# Connectors_-_RP2040_Advanced_Breakout_Bo.net
KiCad netlist of a schematic drawn in EasyEDA
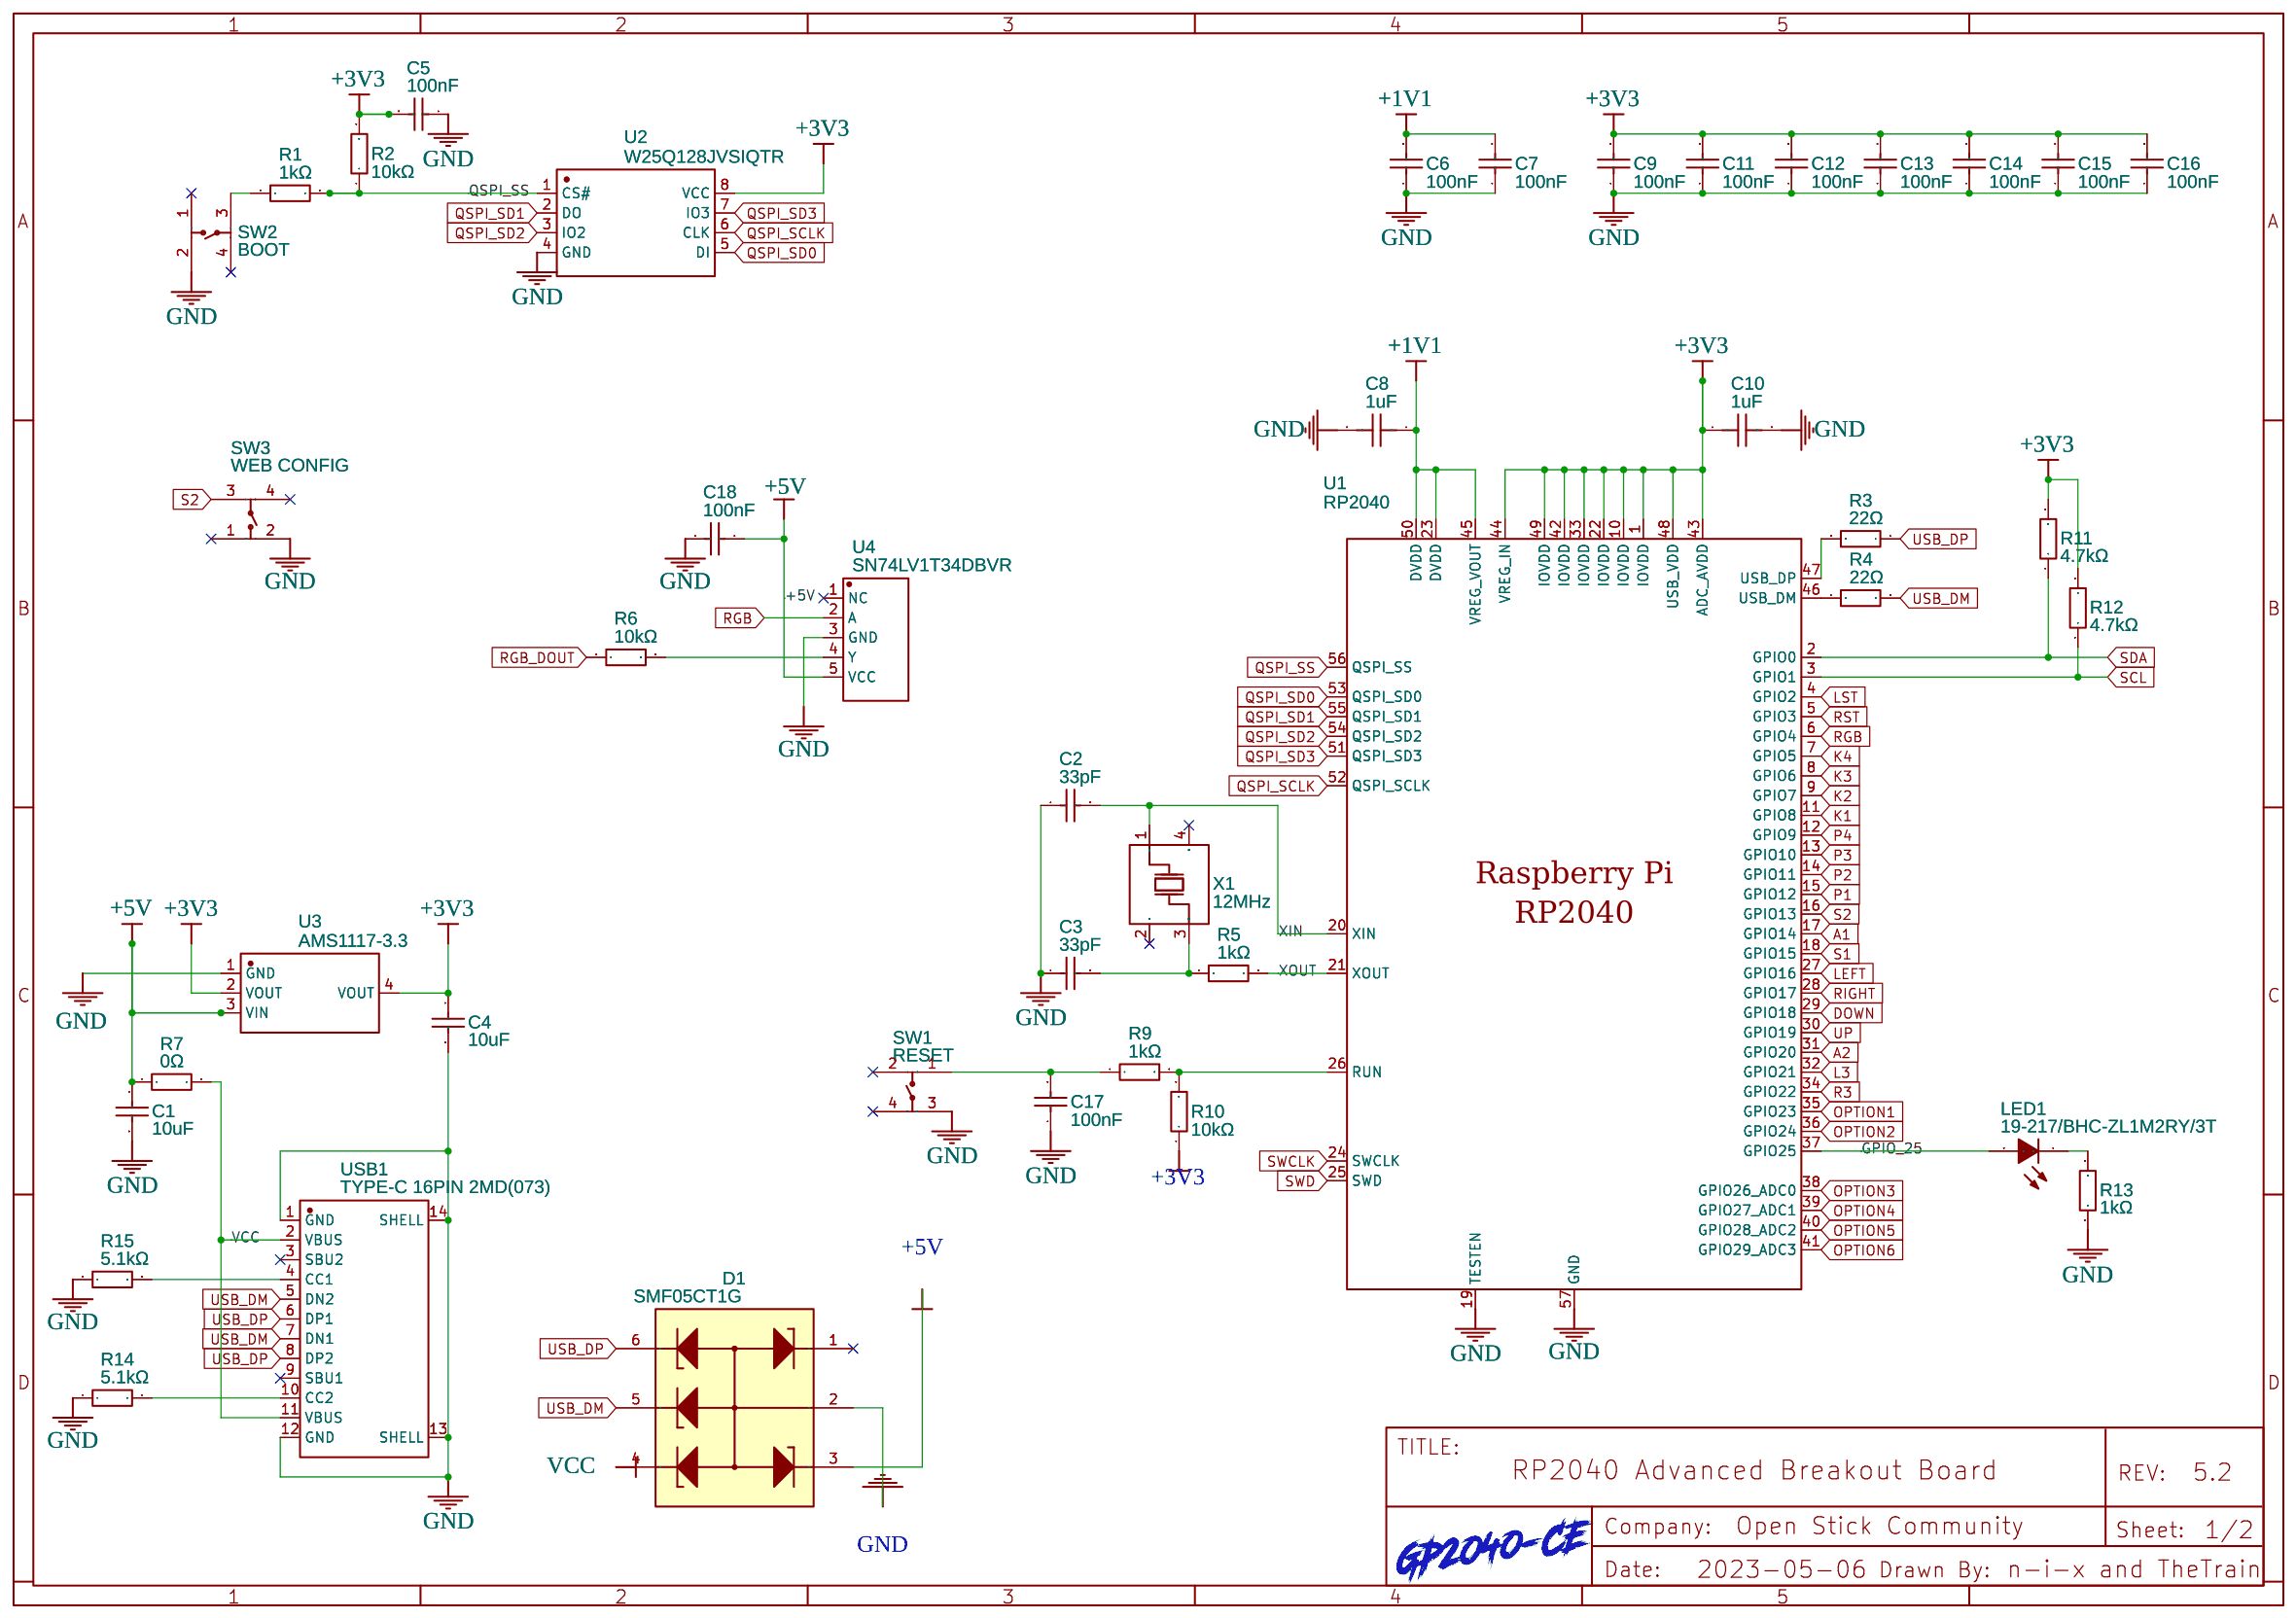
[diagram p0: RP2040 Advanced Breakout Board - Version 5.2E - Schematics]
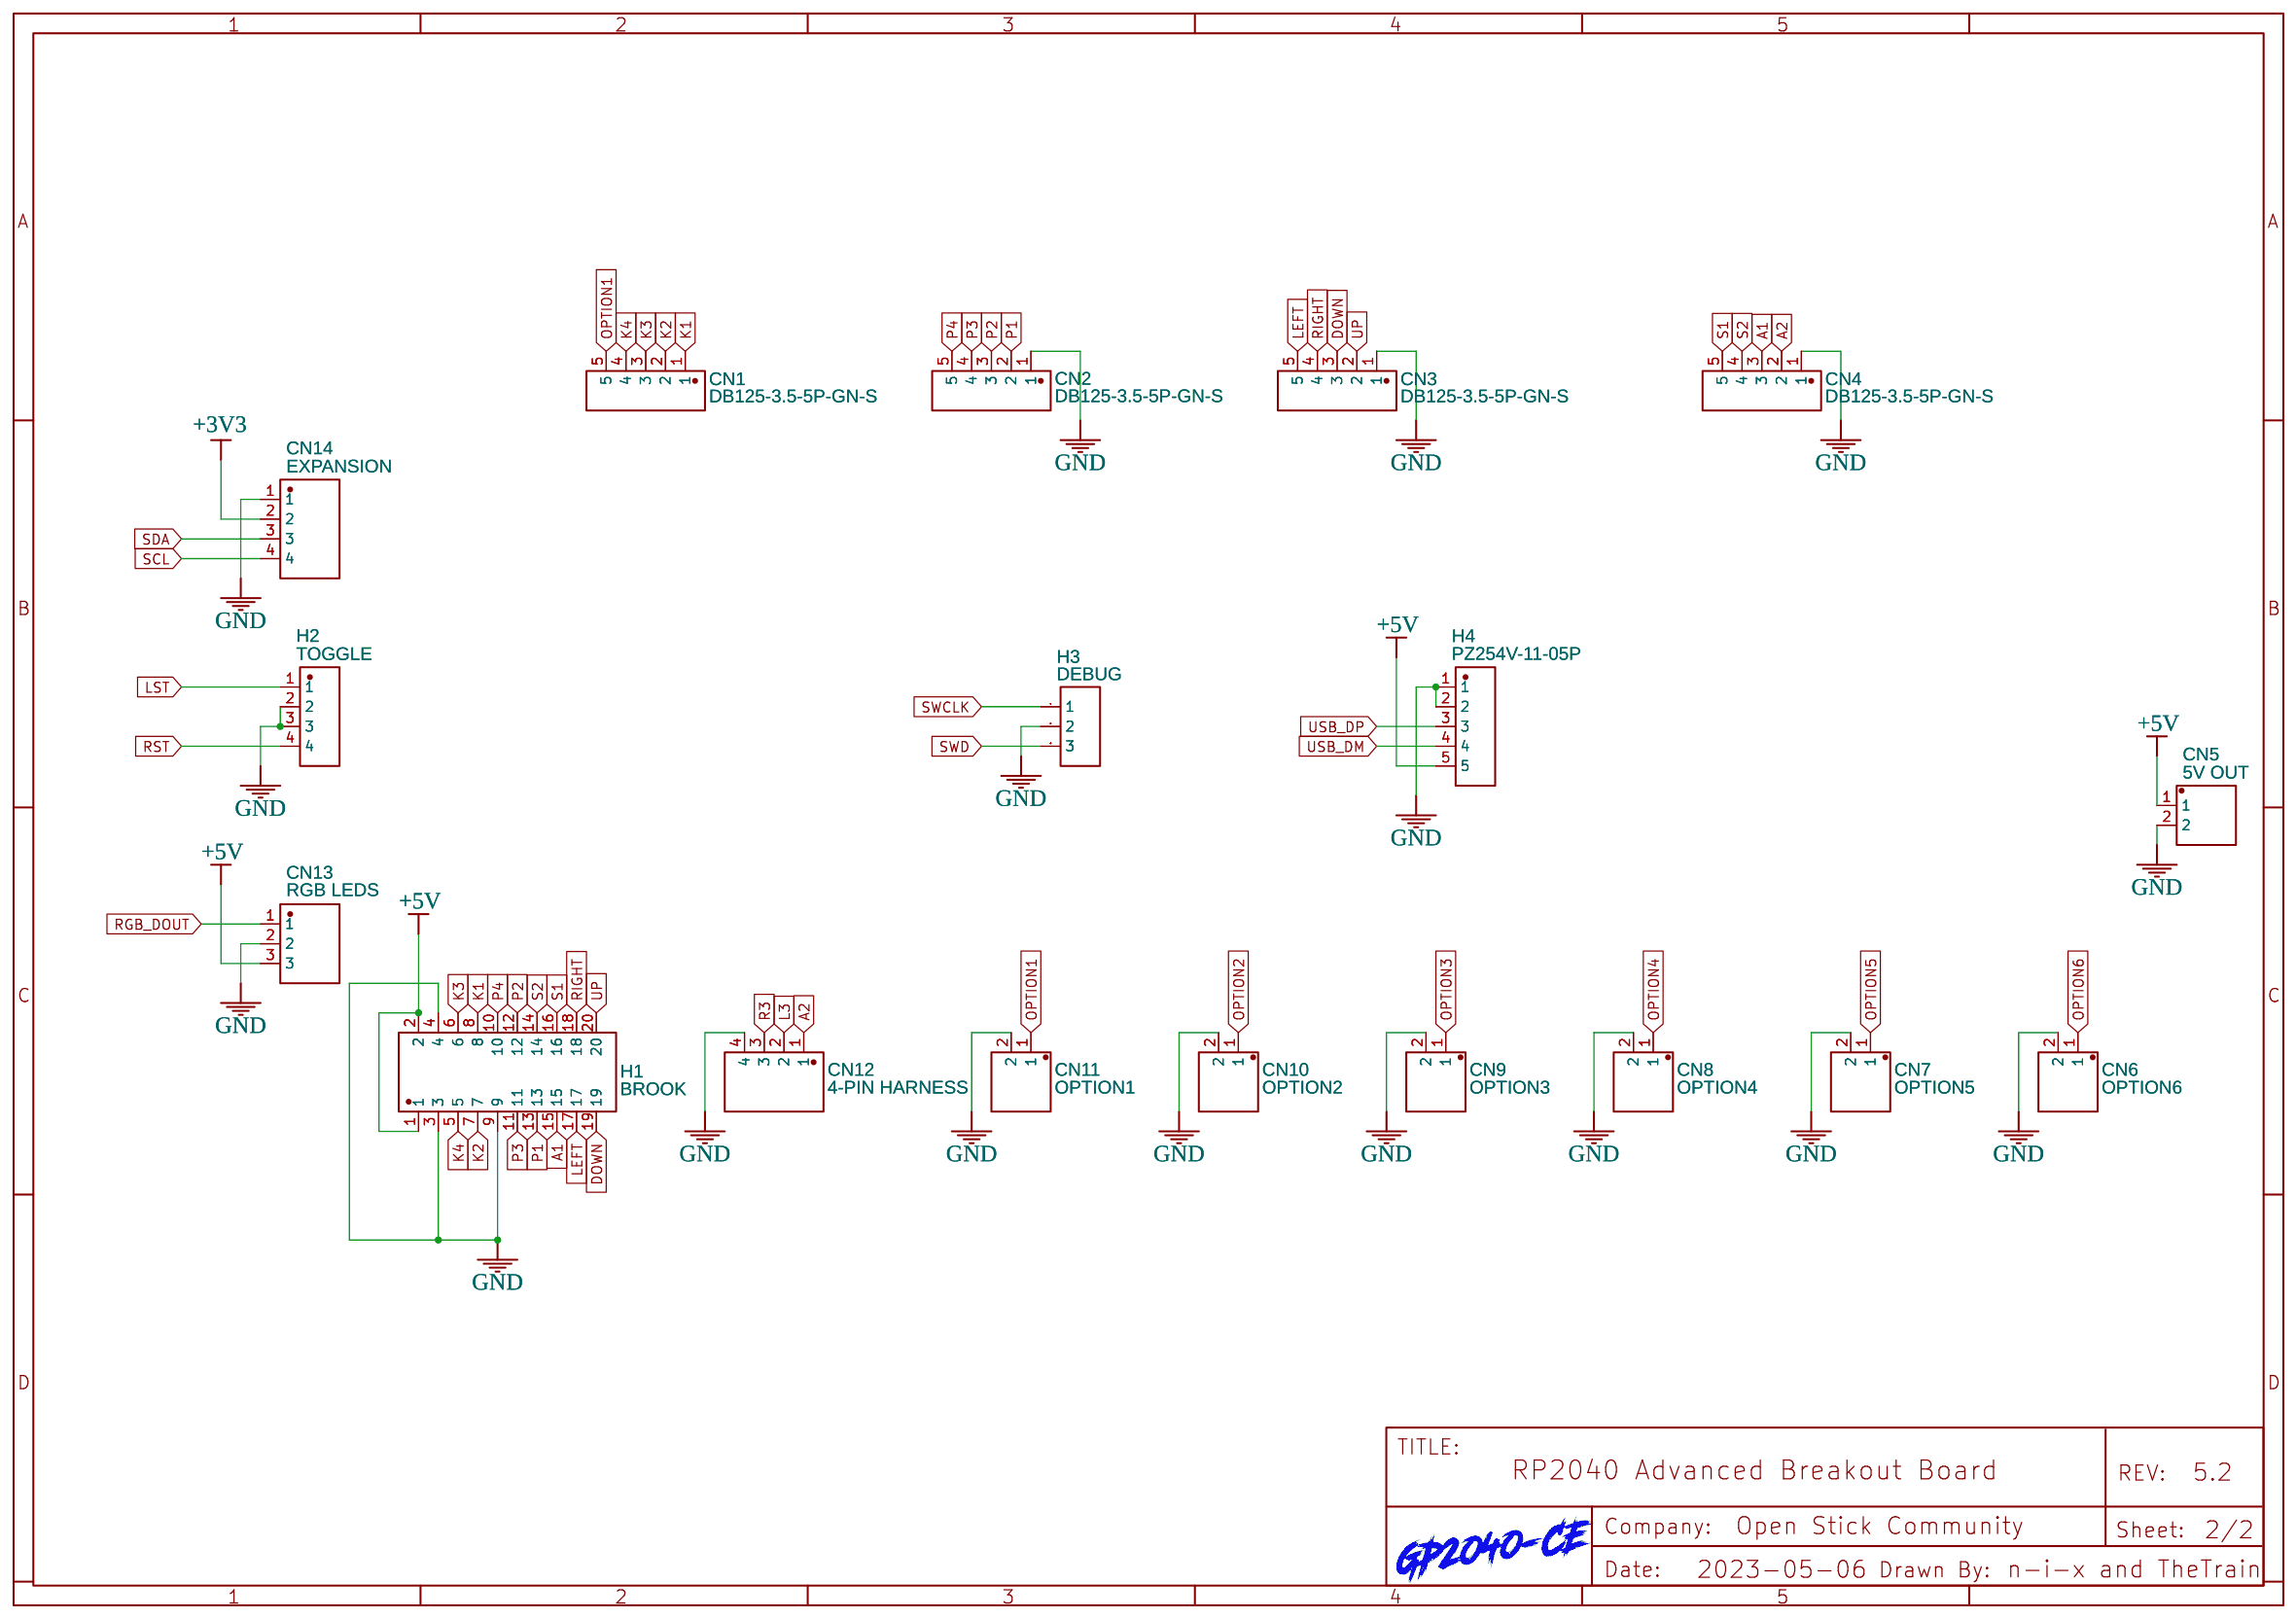
[diagram p1: RP2040 Advanced Breakout Board - Version 5.2E - Connectors]

(export (version "E")
  (design (tool "Eeschema 10.0.6"))
  (components
    (comp (ref "C1")
      (value "10uF")
      (fields
        (field (name "BOM_Manufacturer Part") "CL31A106KBHNNNE")
        (field (name "BOM_Supplier Part") "C13585")
      )
      (libsource (lib "") (part "CL31A106KBHNNNE"))
    )
    (comp (ref "C2")
      (value "33pF")
      (fields
        (field (name "BOM_Manufacturer Part") "0402CG330J500NT")
        (field (name "BOM_Supplier Part") "C1562")
      )
      (libsource (lib "") (part "0402CG330J500NT"))
    )
    (comp (ref "C3")
      (value "33pF")
      (fields
        (field (name "BOM_Manufacturer Part") "0402CG330J500NT")
        (field (name "BOM_Supplier Part") "C1562")
      )
      (libsource (lib "") (part "0402CG330J500NT"))
    )
    (comp (ref "C4")
      (value "10uF")
      (fields
        (field (name "BOM_Manufacturer Part") "CL31A106KBHNNNE")
        (field (name "BOM_Supplier Part") "C13585")
      )
      (libsource (lib "") (part "CL31A106KBHNNNE"))
    )
    (comp (ref "C5")
      (value "100nF")
      (fields
        (field (name "BOM_Manufacturer Part") "CL05B104KO5NNNC")
        (field (name "BOM_Supplier Part") "C1525")
      )
      (libsource (lib "") (part "CL05B104KO5NNNC_2"))
    )
    (comp (ref "C6")
      (value "100nF")
      (fields
        (field (name "BOM_Manufacturer Part") "CL05B104KO5NNNC")
        (field (name "BOM_Supplier Part") "C1525")
      )
      (libsource (lib "") (part "CL05B104KO5NNNC"))
    )
    (comp (ref "C7")
      (value "100nF")
      (fields
        (field (name "BOM_Manufacturer Part") "CL05B104KO5NNNC")
        (field (name "BOM_Supplier Part") "C1525")
      )
      (libsource (lib "") (part "CL05B104KO5NNNC"))
    )
    (comp (ref "C8")
      (value "1uF")
      (fields
        (field (name "BOM_Manufacturer Part") "CL05A105KA5NQNC")
        (field (name "BOM_Supplier Part") "C52923")
      )
      (libsource (lib "") (part "CL05A105KA5NQNC"))
    )
    (comp (ref "C9")
      (value "100nF")
      (fields
        (field (name "BOM_Manufacturer Part") "CL05B104KO5NNNC")
        (field (name "BOM_Supplier Part") "C1525")
      )
      (libsource (lib "") (part "CL05B104KO5NNNC"))
    )
    (comp (ref "C10")
      (value "1uF")
      (fields
        (field (name "BOM_Manufacturer Part") "CL05A105KA5NQNC")
        (field (name "BOM_Supplier Part") "C52923")
      )
      (libsource (lib "") (part "CL05A105KA5NQNC_1"))
    )
    (comp (ref "C11")
      (value "100nF")
      (fields
        (field (name "BOM_Manufacturer Part") "CL05B104KO5NNNC")
        (field (name "BOM_Supplier Part") "C1525")
      )
      (libsource (lib "") (part "CL05B104KO5NNNC"))
    )
    (comp (ref "C12")
      (value "100nF")
      (fields
        (field (name "BOM_Manufacturer Part") "CL05B104KO5NNNC")
        (field (name "BOM_Supplier Part") "C1525")
      )
      (libsource (lib "") (part "CL05B104KO5NNNC"))
    )
    (comp (ref "C13")
      (value "100nF")
      (fields
        (field (name "BOM_Manufacturer Part") "CL05B104KO5NNNC")
        (field (name "BOM_Supplier Part") "C1525")
      )
      (libsource (lib "") (part "CL05B104KO5NNNC"))
    )
    (comp (ref "C14")
      (value "100nF")
      (fields
        (field (name "BOM_Manufacturer Part") "CL05B104KO5NNNC")
        (field (name "BOM_Supplier Part") "C1525")
      )
      (libsource (lib "") (part "CL05B104KO5NNNC"))
    )
    (comp (ref "C15")
      (value "100nF")
      (fields
        (field (name "BOM_Manufacturer Part") "CL05B104KO5NNNC")
        (field (name "BOM_Supplier Part") "C1525")
      )
      (libsource (lib "") (part "CL05B104KO5NNNC"))
    )
    (comp (ref "C16")
      (value "100nF")
      (fields
        (field (name "BOM_Manufacturer Part") "CL05B104KO5NNNC")
        (field (name "BOM_Supplier Part") "C1525")
      )
      (libsource (lib "") (part "CL05B104KO5NNNC"))
    )
    (comp (ref "C17")
      (value "100nF")
      (fields
        (field (name "BOM_Manufacturer Part") "CL05B104KO5NNNC")
        (field (name "BOM_Supplier Part") "C1525")
      )
      (libsource (lib "") (part "CL05B104KO5NNNC"))
    )
    (comp (ref "C18")
      (value "100nF")
      (fields
        (field (name "BOM_Manufacturer Part") "CL05B104KO5NNNC")
        (field (name "BOM_Supplier Part") "C1525")
      )
      (libsource (lib "") (part "CL05B104KO5NNNC_1"))
    )
    (comp (ref "D1")
      (value "SMF05CT1G")
      (fields (field (name "BOM_Supplier Part") "C15879"))
      (libsource (lib "") (part "SMF05CT1G"))
    )
    (comp (ref "LED1")
      (value "19-217/BHC-ZL1M2RY/3T")
      (fields (field (name "BOM_Supplier Part") "C72041"))
      (libsource (lib "") (part "19-217/BHC-ZL1M2RY/3T"))
    )
    (comp (ref "R1")
      (value "1kΩ")
      (fields
        (field (name "BOM_Manufacturer Part") "0402WGF1001TCE")
        (field (name "BOM_Supplier Part") "C11702")
      )
      (libsource (lib "") (part "0402WGF1001TCE"))
    )
    (comp (ref "R2")
      (value "10kΩ")
      (fields
        (field (name "BOM_Manufacturer Part") "0402WGF1002TCE")
        (field (name "BOM_Supplier Part") "C25744")
      )
      (libsource (lib "") (part "0402WGF1002TCE"))
    )
    (comp (ref "R3")
      (value "22Ω")
      (fields
        (field (name "BOM_Manufacturer Part") "0402WGF220JTCE")
        (field (name "BOM_Supplier Part") "C25092")
      )
      (libsource (lib "") (part "0402WGF220JTCE"))
    )
    (comp (ref "R4")
      (value "22Ω")
      (fields
        (field (name "BOM_Manufacturer Part") "0402WGF220JTCE")
        (field (name "BOM_Supplier Part") "C25092")
      )
      (libsource (lib "") (part "0402WGF220JTCE_1"))
    )
    (comp (ref "R5")
      (value "1kΩ")
      (fields
        (field (name "BOM_Manufacturer Part") "0402WGF1001TCE")
        (field (name "BOM_Supplier Part") "C11702")
      )
      (libsource (lib "") (part "0402WGF1001TCE"))
    )
    (comp (ref "R6")
      (value "10kΩ")
      (fields
        (field (name "BOM_Manufacturer Part") "0402WGF1002TCE")
        (field (name "BOM_Supplier Part") "C25744")
      )
      (libsource (lib "") (part "0402WGF1002TCE_1"))
    )
    (comp (ref "R7")
      (value "0Ω")
      (fields
        (field (name "BOM_Manufacturer Part") "0603WAF0000T5E")
        (field (name "BOM_Supplier Part") "C21189")
      )
      (libsource (lib "") (part "0603WAF0000T5E"))
    )
    (comp (ref "R9")
      (value "1kΩ")
      (fields
        (field (name "BOM_Manufacturer Part") "0402WGF1001TCE")
        (field (name "BOM_Supplier Part") "C11702")
      )
      (libsource (lib "") (part "0402WGF1001TCE"))
    )
    (comp (ref "R10")
      (value "10kΩ")
      (fields
        (field (name "BOM_Manufacturer Part") "0402WGF1002TCE")
        (field (name "BOM_Supplier Part") "C25744")
      )
      (libsource (lib "") (part "0402WGF1002TCE"))
    )
    (comp (ref "R11")
      (value "4.7kΩ")
      (fields
        (field (name "BOM_Manufacturer Part") "0603WAF4701T5E")
        (field (name "BOM_Supplier Part") "C23162")
      )
      (libsource (lib "") (part "0603WAF4701T5E"))
    )
    (comp (ref "R12")
      (value "4.7kΩ")
      (fields
        (field (name "BOM_Manufacturer Part") "0603WAF4701T5E")
        (field (name "BOM_Supplier Part") "C23162")
      )
      (libsource (lib "") (part "0603WAF4701T5E"))
    )
    (comp (ref "R13")
      (value "1kΩ")
      (fields
        (field (name "BOM_Manufacturer Part") "0402WGF1001TCE")
        (field (name "BOM_Supplier Part") "C11702")
      )
      (libsource (lib "") (part "0402WGF1001TCE_1"))
    )
    (comp (ref "R14")
      (value "5.1kΩ")
      (fields
        (field (name "BOM_Manufacturer Part") "0402WGF5101TCE")
        (field (name "BOM_Supplier Part") "C25905")
      )
      (libsource (lib "") (part "0402WGF5101TCE"))
    )
    (comp (ref "R15")
      (value "5.1kΩ")
      (fields
        (field (name "BOM_Manufacturer Part") "0402WGF5101TCE")
        (field (name "BOM_Supplier Part") "C25905")
      )
      (libsource (lib "") (part "0402WGF5101TCE"))
    )
    (comp (ref "SW1")
      (value "RESET")
      (fields
        (field (name "BOM_Manufacturer Part") "TD-1182SA-2.0H-250")
        (field (name "BOM_Supplier Part") "C2905178")
      )
      (libsource (lib "") (part "TD-1182SA-2.0H-250"))
    )
    (comp (ref "SW2")
      (value "BOOT")
      (fields
        (field (name "BOM_Manufacturer Part") "TD-1182SA-2.0H-250")
        (field (name "BOM_Supplier Part") "C2905178")
      )
      (libsource (lib "") (part "TD-1182SA-2.0H-250_2"))
    )
    (comp (ref "SW3")
      (value "WEB CONFIG")
      (fields
        (field (name "BOM_Manufacturer Part") "TD-1182SA-2.0H-250")
        (field (name "BOM_Supplier Part") "C2905178")
      )
      (libsource (lib "") (part "TD-1182SA-2.0H-250_1"))
    )
    (comp (ref "U1")
      (value "RP2040")
      (fields (field (name "BOM_Supplier Part") "C2040"))
      (libsource (lib "") (part "RP2040"))
    )
    (comp (ref "U2")
      (value "W25Q128JVSIQTR")
      (fields
        (field (name "BOM_Manufacturer Part") "W25Q128JVSIQ")
        (field (name "BOM_Supplier Part") "C97521")
      )
      (libsource (lib "") (part "W25Q128JVSIQTR"))
    )
    (comp (ref "U3")
      (value "AMS1117-3.3")
      (fields (field (name "BOM_Supplier Part") "C6186"))
      (libsource (lib "") (part "AMS1117-3.3"))
    )
    (comp (ref "U4")
      (value "SN74LV1T34DBVR")
      (fields (field (name "BOM_Supplier Part") "C100024"))
      (libsource (lib "") (part "SN74LV1T34DBVR"))
    )
    (comp (ref "USB1")
      (value "TYPE-C 16PIN 2MD(073)")
      (fields (field (name "BOM_Supplier Part") "C2765186"))
      (libsource (lib "") (part "TYPE-C 16PIN 2MD(073)"))
    )
    (comp (ref "X1")
      (value "12MHz")
      (fields
        (field (name "BOM_Manufacturer Part") "X322512MSB4SI")
        (field (name "BOM_Supplier Part") "C9002")
      )
      (libsource (lib "") (part "X322512MSB4SI"))
    )
    (comp (ref "CN1")
      (value "DB125-3.5-5P-GN-S")
      (fields (field (name "BOM_Supplier Part") "C3646874"))
      (libsource (lib "") (part "DB125-3.5-5P-GN-S"))
    )
    (comp (ref "CN2")
      (value "DB125-3.5-5P-GN-S")
      (fields (field (name "BOM_Supplier Part") "C3646874"))
      (libsource (lib "") (part "DB125-3.5-5P-GN-S"))
    )
    (comp (ref "CN3")
      (value "DB125-3.5-5P-GN-S")
      (fields (field (name "BOM_Supplier Part") "C3646874"))
      (libsource (lib "") (part "DB125-3.5-5P-GN-S"))
    )
    (comp (ref "CN4")
      (value "DB125-3.5-5P-GN-S")
      (fields (field (name "BOM_Supplier Part") "C3646874"))
      (libsource (lib "") (part "DB125-3.5-5P-GN-S"))
    )
    (comp (ref "CN5")
      (value "5V OUT")
      (fields
        (field (name "BOM_Manufacturer Part") "S2B-PH-K-S(LF)(SN)")
        (field (name "BOM_Supplier Part") "C173752")
      )
      (libsource (lib "") (part "S2B-PH-K-S(LF)(SN)_1"))
    )
    (comp (ref "CN6")
      (value "OPTION6")
      (fields
        (field (name "BOM_Manufacturer Part") "S2B-PH-K-S(LF)(SN)")
        (field (name "BOM_Supplier Part") "C173752")
      )
      (libsource (lib "") (part "S2B-PH-K-S(LF)(SN)"))
    )
    (comp (ref "CN7")
      (value "OPTION5")
      (fields
        (field (name "BOM_Manufacturer Part") "S2B-PH-K-S(LF)(SN)")
        (field (name "BOM_Supplier Part") "C173752")
      )
      (libsource (lib "") (part "S2B-PH-K-S(LF)(SN)"))
    )
    (comp (ref "CN8")
      (value "OPTION4")
      (fields
        (field (name "BOM_Manufacturer Part") "S2B-PH-K-S(LF)(SN)")
        (field (name "BOM_Supplier Part") "C173752")
      )
      (libsource (lib "") (part "S2B-PH-K-S(LF)(SN)"))
    )
    (comp (ref "CN9")
      (value "OPTION3")
      (fields
        (field (name "BOM_Manufacturer Part") "S2B-PH-K-S(LF)(SN)")
        (field (name "BOM_Supplier Part") "C173752")
      )
      (libsource (lib "") (part "S2B-PH-K-S(LF)(SN)"))
    )
    (comp (ref "CN10")
      (value "OPTION2")
      (fields
        (field (name "BOM_Manufacturer Part") "S2B-PH-K-S(LF)(SN)")
        (field (name "BOM_Supplier Part") "C173752")
      )
      (libsource (lib "") (part "S2B-PH-K-S(LF)(SN)"))
    )
    (comp (ref "CN11")
      (value "OPTION1")
      (fields
        (field (name "BOM_Manufacturer Part") "S2B-PH-K-S(LF)(SN)")
        (field (name "BOM_Supplier Part") "C173752")
      )
      (libsource (lib "") (part "S2B-PH-K-S(LF)(SN)"))
    )
    (comp (ref "CN12")
      (value "4-PIN HARNESS")
      (fields
        (field (name "BOM_Manufacturer Part") "S4B-PH-K-S(LF)(SN)")
        (field (name "BOM_Supplier Part") "C157926")
      )
      (libsource (lib "") (part "S4B-PH-K-S-(LF)(SN)"))
    )
    (comp (ref "CN13")
      (value "RGB LEDS")
      (fields
        (field (name "BOM_Manufacturer Part") "S3B-PH-K-S(LF)(SN)")
        (field (name "BOM_Supplier Part") "C157929")
      )
      (libsource (lib "") (part "S3B-PH-K-S-(LF)(SN)"))
    )
    (comp (ref "CN14")
      (value "EXPANSION")
      (fields
        (field (name "BOM_Manufacturer Part") "S4B-PH-K-S(LF)(SN)")
        (field (name "BOM_Supplier Part") "C157926")
      )
      (libsource (lib "") (part "S4B-PH-K-S-(LF)(SN)_1"))
    )
    (comp (ref "H1")
      (value "BROOK")
      (fields
        (field (name "BOM_Manufacturer Part") "PZ254V-12-20P")
        (field (name "BOM_Supplier Part") "C492427")
      )
      (libsource (lib "") (part "PZ254V-12-20P"))
    )
    (comp (ref "H2")
      (value "TOGGLE")
      (fields
        (field (name "BOM_Manufacturer Part") "2.54-1*4P反弯排针")
        (field (name "BOM_Supplier Part") "C91552")
      )
      (libsource (lib "") (part "2.54-1*4P反弯排针"))
    )
    (comp (ref "H3")
      (value "DEBUG")
      (fields (field (name "BOM_Manufacturer Part") "2.54-1*3P针") (field (name "BOM_Supplier Part") "C49257"))
      (libsource (lib "") (part "Header-Male-2.54_1x3"))
    )
    (comp (ref "H4")
      (value "PZ254V-11-05P")
      (fields (field (name "BOM_Supplier Part") "C492404"))
      (libsource (lib "") (part "PZ254V-11-05P"))
    )
  )
  (nets
    (net (code "1") (name "+1V1") (class "Default")
      (node (ref "C6") (pin "2") (pinfunction "2_2") (pintype "input"))
      (node (ref "C7") (pin "2") (pinfunction "2_2") (pintype "input"))
      (node (ref "C8") (pin "1") (pinfunction "1_1") (pintype "unspecified"))
      (node (ref "U1") (pin "23") (pinfunction "DVDD_23") (pintype "bidirectional"))
      (node (ref "U1") (pin "45") (pinfunction "VREG_VOUT_45") (pintype "bidirectional"))
      (node (ref "U1") (pin "50") (pinfunction "DVDD_50") (pintype "bidirectional"))
    )
    (net (code "2") (name "+3V3") (class "Default")
      (node (ref "C10") (pin "1") (pinfunction "1_1") (pintype "unspecified"))
      (node (ref "C11") (pin "2") (pinfunction "2_2") (pintype "input"))
      (node (ref "C12") (pin "2") (pinfunction "2_2") (pintype "input"))
      (node (ref "C13") (pin "2") (pinfunction "2_2") (pintype "input"))
      (node (ref "C14") (pin "2") (pinfunction "2_2") (pintype "input"))
      (node (ref "C15") (pin "2") (pinfunction "2_2") (pintype "input"))
      (node (ref "C16") (pin "2") (pinfunction "2_2") (pintype "input"))
      (node (ref "C4") (pin "1") (pinfunction "1_1") (pintype "input"))
      (node (ref "C5") (pin "2") (pinfunction "2_2") (pintype "input"))
      (node (ref "C9") (pin "2") (pinfunction "2_2") (pintype "input"))
      (node (ref "CN14") (pin "2") (pinfunction "2_2") (pintype "unspecified"))
      (node (ref "R10") (pin "1") (pinfunction "1_1") (pintype "input"))
      (node (ref "R11") (pin "2") (pinfunction "2_2") (pintype "input"))
      (node (ref "R12") (pin "2") (pinfunction "2_2") (pintype "input"))
      (node (ref "R2") (pin "2") (pinfunction "2_2") (pintype "input"))
      (node (ref "U1") (pin "1") (pinfunction "IOVDD_1") (pintype "bidirectional"))
      (node (ref "U1") (pin "10") (pinfunction "IOVDD_10") (pintype "bidirectional"))
      (node (ref "U1") (pin "22") (pinfunction "IOVDD_22") (pintype "bidirectional"))
      (node (ref "U1") (pin "33") (pinfunction "IOVDD_33") (pintype "bidirectional"))
      (node (ref "U1") (pin "42") (pinfunction "IOVDD_42") (pintype "bidirectional"))
      (node (ref "U1") (pin "43") (pinfunction "ADC_AVDD_43") (pintype "bidirectional"))
      (node (ref "U1") (pin "44") (pinfunction "VREG_IN_44") (pintype "bidirectional"))
      (node (ref "U1") (pin "48") (pinfunction "USB_VDD_48") (pintype "bidirectional"))
      (node (ref "U1") (pin "49") (pinfunction "IOVDD_49") (pintype "bidirectional"))
      (node (ref "U2") (pin "8") (pinfunction "VCC_8") (pintype "unspecified"))
      (node (ref "U3") (pin "2") (pinfunction "VOUT_2") (pintype "unspecified"))
      (node (ref "U3") (pin "4") (pinfunction "VOUT_4") (pintype "unspecified"))
    )
    (net (code "3") (name "+5V") (class "Default")
      (node (ref "C1") (pin "1") (pinfunction "1_1") (pintype "input"))
      (node (ref "C18") (pin "2") (pinfunction "2_2") (pintype "input"))
      (node (ref "CN13") (pin "3") (pinfunction "3_3") (pintype "unspecified"))
      (node (ref "CN5") (pin "1") (pinfunction "1_1") (pintype "unspecified"))
      (node (ref "D1") (pin "3") (pinfunction "3_3") (pintype "input"))
      (node (ref "H1") (pin "1") (pinfunction "1_1") (pintype "unspecified"))
      (node (ref "H1") (pin "2") (pinfunction "2_2") (pintype "unspecified"))
      (node (ref "H4") (pin "5") (pinfunction "5_5") (pintype "unspecified"))
      (node (ref "R7") (pin "1") (pinfunction "1_1") (pintype "input"))
      (node (ref "U3") (pin "3") (pinfunction "VIN_3") (pintype "unspecified"))
      (node (ref "U4") (pin "5") (pinfunction "VCC_5") (pintype "unspecified"))
    )
    (net (code "4") (name "A1") (class "Default")
      (node (ref "CN4") (pin "3") (pinfunction "3_3") (pintype "unspecified"))
      (node (ref "H1") (pin "15") (pinfunction "15_15") (pintype "unspecified"))
      (node (ref "U1") (pin "17") (pinfunction "GPIO14_17") (pintype "bidirectional"))
    )
    (net (code "5") (name "A2") (class "Default")
      (node (ref "CN12") (pin "1") (pinfunction "1_1") (pintype "unspecified"))
      (node (ref "CN4") (pin "2") (pinfunction "2_2") (pintype "unspecified"))
      (node (ref "U1") (pin "31") (pinfunction "GPIO20_31") (pintype "bidirectional"))
    )
    (net (code "6") (name "DOWN") (class "Default")
      (node (ref "CN3") (pin "3") (pinfunction "3_3") (pintype "unspecified"))
      (node (ref "H1") (pin "19") (pinfunction "19_19") (pintype "unspecified"))
      (node (ref "U1") (pin "29") (pinfunction "GPIO18_29") (pintype "bidirectional"))
    )
    (net (code "7") (name "GND") (class "Default")
      (node (ref "C1") (pin "2") (pinfunction "2_2") (pintype "input"))
      (node (ref "C10") (pin "2") (pinfunction "2_2") (pintype "unspecified"))
      (node (ref "C11") (pin "1") (pinfunction "1_1") (pintype "input"))
      (node (ref "C12") (pin "1") (pinfunction "1_1") (pintype "input"))
      (node (ref "C13") (pin "1") (pinfunction "1_1") (pintype "input"))
      (node (ref "C14") (pin "1") (pinfunction "1_1") (pintype "input"))
      (node (ref "C15") (pin "1") (pinfunction "1_1") (pintype "input"))
      (node (ref "C16") (pin "1") (pinfunction "1_1") (pintype "input"))
      (node (ref "C17") (pin "1") (pinfunction "1_1") (pintype "input"))
      (node (ref "C18") (pin "1") (pinfunction "1_1") (pintype "input"))
      (node (ref "C2") (pin "1") (pinfunction "1_1") (pintype "input"))
      (node (ref "C3") (pin "1") (pinfunction "1_1") (pintype "input"))
      (node (ref "C4") (pin "2") (pinfunction "2_2") (pintype "input"))
      (node (ref "C5") (pin "1") (pinfunction "1_1") (pintype "input"))
      (node (ref "C6") (pin "1") (pinfunction "1_1") (pintype "input"))
      (node (ref "C7") (pin "1") (pinfunction "1_1") (pintype "input"))
      (node (ref "C8") (pin "2") (pinfunction "2_2") (pintype "unspecified"))
      (node (ref "C9") (pin "1") (pinfunction "1_1") (pintype "input"))
      (node (ref "CN10") (pin "2") (pinfunction "2_2") (pintype "unspecified"))
      (node (ref "CN11") (pin "2") (pinfunction "2_2") (pintype "unspecified"))
      (node (ref "CN12") (pin "4") (pinfunction "4_4") (pintype "unspecified"))
      (node (ref "CN13") (pin "2") (pinfunction "2_2") (pintype "unspecified"))
      (node (ref "CN14") (pin "1") (pinfunction "1_1") (pintype "unspecified"))
      (node (ref "CN2") (pin "1") (pinfunction "1_1") (pintype "unspecified"))
      (node (ref "CN3") (pin "1") (pinfunction "1_1") (pintype "unspecified"))
      (node (ref "CN4") (pin "1") (pinfunction "1_1") (pintype "unspecified"))
      (node (ref "CN5") (pin "2") (pinfunction "2_2") (pintype "unspecified"))
      (node (ref "CN6") (pin "2") (pinfunction "2_2") (pintype "unspecified"))
      (node (ref "CN7") (pin "2") (pinfunction "2_2") (pintype "unspecified"))
      (node (ref "CN8") (pin "2") (pinfunction "2_2") (pintype "unspecified"))
      (node (ref "CN9") (pin "2") (pinfunction "2_2") (pintype "unspecified"))
      (node (ref "D1") (pin "2") (pinfunction "2_2") (pintype "input"))
      (node (ref "H1") (pin "3") (pinfunction "3_3") (pintype "unspecified"))
      (node (ref "H1") (pin "4") (pinfunction "4_4") (pintype "unspecified"))
      (node (ref "H1") (pin "9") (pinfunction "9_9") (pintype "unspecified"))
      (node (ref "H2") (pin "2") (pinfunction "2_2") (pintype "unspecified"))
      (node (ref "H2") (pin "3") (pinfunction "3_3") (pintype "unspecified"))
      (node (ref "H3") (pin "2") (pinfunction "2_2") (pintype "input"))
      (node (ref "H4") (pin "1") (pinfunction "1_1") (pintype "unspecified"))
      (node (ref "H4") (pin "2") (pinfunction "2_2") (pintype "unspecified"))
      (node (ref "R13") (pin "1") (pinfunction "1_1") (pintype "input"))
      (node (ref "R14") (pin "1") (pinfunction "1_1") (pintype "input"))
      (node (ref "R15") (pin "1") (pinfunction "1_1") (pintype "input"))
      (node (ref "SW1") (pin "3") (pinfunction "3_3") (pintype "unspecified"))
      (node (ref "SW2") (pin "2") (pinfunction "2_2") (pintype "unspecified"))
      (node (ref "SW3") (pin "2") (pinfunction "2_2") (pintype "unspecified"))
      (node (ref "U1") (pin "19") (pinfunction "TESTEN_19") (pintype "unspecified"))
      (node (ref "U1") (pin "57") (pinfunction "GND_57") (pintype "bidirectional"))
      (node (ref "U2") (pin "4") (pinfunction "GND_4") (pintype "unspecified"))
      (node (ref "U3") (pin "1") (pinfunction "GND_1") (pintype "unspecified"))
      (node (ref "U4") (pin "3") (pinfunction "GND_3") (pintype "unspecified"))
      (node (ref "USB1") (pin "1") (pinfunction "GND_1") (pintype "unspecified"))
      (node (ref "USB1") (pin "12") (pinfunction "GND_12") (pintype "unspecified"))
      (node (ref "USB1") (pin "13") (pinfunction "SHELL_13") (pintype "unspecified"))
      (node (ref "USB1") (pin "14") (pinfunction "SHELL_14") (pintype "unspecified"))
    )
    (net (code "8") (name "GPIO_25") (class "Default")
      (node (ref "LED1") (pin "2") (pinfunction "A_2") (pintype "input"))
      (node (ref "U1") (pin "37") (pinfunction "GPIO25_37") (pintype "bidirectional"))
    )
    (net (code "9") (name "K1") (class "Default")
      (node (ref "CN1") (pin "1") (pinfunction "1_1") (pintype "unspecified"))
      (node (ref "H1") (pin "8") (pinfunction "8_8") (pintype "unspecified"))
      (node (ref "U1") (pin "11") (pinfunction "GPIO8_11") (pintype "bidirectional"))
    )
    (net (code "10") (name "K2") (class "Default")
      (node (ref "CN1") (pin "2") (pinfunction "2_2") (pintype "unspecified"))
      (node (ref "H1") (pin "7") (pinfunction "7_7") (pintype "unspecified"))
      (node (ref "U1") (pin "9") (pinfunction "GPIO7_9") (pintype "bidirectional"))
    )
    (net (code "11") (name "K3") (class "Default")
      (node (ref "CN1") (pin "3") (pinfunction "3_3") (pintype "unspecified"))
      (node (ref "H1") (pin "6") (pinfunction "6_6") (pintype "unspecified"))
      (node (ref "U1") (pin "8") (pinfunction "GPIO6_8") (pintype "bidirectional"))
    )
    (net (code "12") (name "K4") (class "Default")
      (node (ref "CN1") (pin "4") (pinfunction "4_4") (pintype "unspecified"))
      (node (ref "H1") (pin "5") (pinfunction "5_5") (pintype "unspecified"))
      (node (ref "U1") (pin "7") (pinfunction "GPIO5_7") (pintype "bidirectional"))
    )
    (net (code "13") (name "L3") (class "Default")
      (node (ref "CN12") (pin "2") (pinfunction "2_2") (pintype "unspecified"))
      (node (ref "U1") (pin "32") (pinfunction "GPIO21_32") (pintype "bidirectional"))
    )
    (net (code "14") (name "LEFT") (class "Default")
      (node (ref "CN3") (pin "5") (pinfunction "5_5") (pintype "unspecified"))
      (node (ref "H1") (pin "17") (pinfunction "17_17") (pintype "unspecified"))
      (node (ref "U1") (pin "27") (pinfunction "GPIO16_27") (pintype "bidirectional"))
    )
    (net (code "15") (name "LST") (class "Default")
      (node (ref "H2") (pin "1") (pinfunction "1_1") (pintype "unspecified"))
      (node (ref "U1") (pin "4") (pinfunction "GPIO2_4") (pintype "bidirectional"))
    )
    (net (code "16") (name "Net-(C17-Pad2)") (class "Default")
      (node (ref "C17") (pin "2") (pinfunction "2_2") (pintype "input"))
      (node (ref "R9") (pin "1") (pinfunction "1_1") (pintype "input"))
      (node (ref "SW1") (pin "1") (pinfunction "1_1") (pintype "unspecified"))
    )
    (net (code "17") (name "Net-(LED1-C)") (class "Default")
      (node (ref "LED1") (pin "1") (pinfunction "C_1") (pintype "input"))
      (node (ref "R13") (pin "2") (pinfunction "2_2") (pintype "input"))
    )
    (net (code "18") (name "Net-(R1-Pad1)") (class "Default")
      (node (ref "R1") (pin "1") (pinfunction "1_1") (pintype "input"))
      (node (ref "SW2") (pin "3") (pinfunction "3_3") (pintype "unspecified"))
    )
    (net (code "19") (name "Net-(U1-RUN)") (class "Default")
      (node (ref "R10") (pin "2") (pinfunction "2_2") (pintype "input"))
      (node (ref "R9") (pin "2") (pinfunction "2_2") (pintype "input"))
      (node (ref "U1") (pin "26") (pinfunction "RUN_26") (pintype "input"))
    )
    (net (code "20") (name "Net-(U1-USB_DM)") (class "Default")
      (node (ref "R4") (pin "1") (pinfunction "1_1") (pintype "input"))
      (node (ref "U1") (pin "46") (pinfunction "USB_DM_46") (pintype "bidirectional"))
    )
    (net (code "21") (name "Net-(U1-USB_DP)") (class "Default")
      (node (ref "R3") (pin "2") (pinfunction "2_2") (pintype "input"))
      (node (ref "U1") (pin "47") (pinfunction "USB_DP_47") (pintype "bidirectional"))
    )
    (net (code "22") (name "Net-(U4-Y)") (class "Default")
      (node (ref "R6") (pin "2") (pinfunction "2_2") (pintype "input"))
      (node (ref "U4") (pin "4") (pinfunction "Y_4") (pintype "unspecified"))
    )
    (net (code "23") (name "Net-(USB1-CC1)") (class "Default")
      (node (ref "R15") (pin "2") (pinfunction "2_2") (pintype "input"))
      (node (ref "USB1") (pin "4") (pinfunction "CC1_4") (pintype "unspecified"))
    )
    (net (code "24") (name "Net-(USB1-CC2)") (class "Default")
      (node (ref "R14") (pin "2") (pinfunction "2_2") (pintype "input"))
      (node (ref "USB1") (pin "10") (pinfunction "CC2_10") (pintype "unspecified"))
    )
    (net (code "25") (name "Net-(X1-OSC2)") (class "Default")
      (node (ref "C3") (pin "2") (pinfunction "2_2") (pintype "input"))
      (node (ref "R5") (pin "1") (pinfunction "1_1") (pintype "input"))
      (node (ref "X1") (pin "3") (pinfunction "OSC2_3") (pintype "unspecified"))
    )
    (net (code "26") (name "OPTION1") (class "Default")
      (node (ref "CN1") (pin "5") (pinfunction "5_5") (pintype "unspecified"))
      (node (ref "CN11") (pin "1") (pinfunction "1_1") (pintype "unspecified"))
      (node (ref "U1") (pin "35") (pinfunction "GPIO23_35") (pintype "bidirectional"))
    )
    (net (code "27") (name "OPTION2") (class "Default")
      (node (ref "CN10") (pin "1") (pinfunction "1_1") (pintype "unspecified"))
      (node (ref "U1") (pin "36") (pinfunction "GPIO24_36") (pintype "bidirectional"))
    )
    (net (code "28") (name "OPTION3") (class "Default")
      (node (ref "CN9") (pin "1") (pinfunction "1_1") (pintype "unspecified"))
      (node (ref "U1") (pin "38") (pinfunction "GPIO26_ADC0_38") (pintype "bidirectional"))
    )
    (net (code "29") (name "OPTION4") (class "Default")
      (node (ref "CN8") (pin "1") (pinfunction "1_1") (pintype "unspecified"))
      (node (ref "U1") (pin "39") (pinfunction "GPIO27_ADC1_39") (pintype "bidirectional"))
    )
    (net (code "30") (name "OPTION5") (class "Default")
      (node (ref "CN7") (pin "1") (pinfunction "1_1") (pintype "unspecified"))
      (node (ref "U1") (pin "40") (pinfunction "GPIO28_ADC2_40") (pintype "bidirectional"))
    )
    (net (code "31") (name "OPTION6") (class "Default")
      (node (ref "CN6") (pin "1") (pinfunction "1_1") (pintype "unspecified"))
      (node (ref "U1") (pin "41") (pinfunction "GPIO29_ADC3_41") (pintype "bidirectional"))
    )
    (net (code "32") (name "P1") (class "Default")
      (node (ref "CN2") (pin "2") (pinfunction "2_2") (pintype "unspecified"))
      (node (ref "H1") (pin "13") (pinfunction "13_13") (pintype "unspecified"))
      (node (ref "U1") (pin "15") (pinfunction "GPIO12_15") (pintype "bidirectional"))
    )
    (net (code "33") (name "P2") (class "Default")
      (node (ref "CN2") (pin "3") (pinfunction "3_3") (pintype "unspecified"))
      (node (ref "H1") (pin "12") (pinfunction "12_12") (pintype "unspecified"))
      (node (ref "U1") (pin "14") (pinfunction "GPIO11_14") (pintype "bidirectional"))
    )
    (net (code "34") (name "P3") (class "Default")
      (node (ref "CN2") (pin "4") (pinfunction "4_4") (pintype "unspecified"))
      (node (ref "H1") (pin "11") (pinfunction "11_11") (pintype "unspecified"))
      (node (ref "U1") (pin "13") (pinfunction "GPIO10_13") (pintype "bidirectional"))
    )
    (net (code "35") (name "P4") (class "Default")
      (node (ref "CN2") (pin "5") (pinfunction "5_5") (pintype "unspecified"))
      (node (ref "H1") (pin "10") (pinfunction "10_10") (pintype "unspecified"))
      (node (ref "U1") (pin "12") (pinfunction "GPIO9_12") (pintype "bidirectional"))
    )
    (net (code "36") (name "QSPI_SCLK") (class "Default")
      (node (ref "U1") (pin "52") (pinfunction "QSPI_SCLK_52") (pintype "output"))
      (node (ref "U2") (pin "6") (pinfunction "CLK_6") (pintype "unspecified"))
    )
    (net (code "37") (name "QSPI_SD0") (class "Default")
      (node (ref "U1") (pin "53") (pinfunction "QSPI_SD0_53") (pintype "bidirectional"))
      (node (ref "U2") (pin "5") (pinfunction "DI_5") (pintype "unspecified"))
    )
    (net (code "38") (name "QSPI_SD1") (class "Default")
      (node (ref "U1") (pin "55") (pinfunction "QSPI_SD1_55") (pintype "bidirectional"))
      (node (ref "U2") (pin "2") (pinfunction "DO_2") (pintype "unspecified"))
    )
    (net (code "39") (name "QSPI_SD2") (class "Default")
      (node (ref "U1") (pin "54") (pinfunction "QSPI_SD2_54") (pintype "bidirectional"))
      (node (ref "U2") (pin "3") (pinfunction "IO2_3") (pintype "unspecified"))
    )
    (net (code "40") (name "QSPI_SD3") (class "Default")
      (node (ref "U1") (pin "51") (pinfunction "QSPI_SD3_51") (pintype "bidirectional"))
      (node (ref "U2") (pin "7") (pinfunction "IO3_7") (pintype "unspecified"))
    )
    (net (code "41") (name "QSPI_SS") (class "Default")
      (node (ref "R1") (pin "2") (pinfunction "2_2") (pintype "input"))
      (node (ref "R2") (pin "1") (pinfunction "1_1") (pintype "input"))
      (node (ref "U1") (pin "56") (pinfunction "QSPI_SS_56") (pintype "bidirectional"))
      (node (ref "U2") (pin "1") (pinfunction "CS#_1") (pintype "unspecified"))
    )
    (net (code "42") (name "R3") (class "Default")
      (node (ref "CN12") (pin "3") (pinfunction "3_3") (pintype "unspecified"))
      (node (ref "U1") (pin "34") (pinfunction "GPIO22_34") (pintype "bidirectional"))
    )
    (net (code "43") (name "RGB") (class "Default")
      (node (ref "U1") (pin "6") (pinfunction "GPIO4_6") (pintype "bidirectional"))
      (node (ref "U4") (pin "2") (pinfunction "A_2") (pintype "unspecified"))
    )
    (net (code "44") (name "RGB_DOUT") (class "Default")
      (node (ref "CN13") (pin "1") (pinfunction "1_1") (pintype "unspecified"))
      (node (ref "R6") (pin "1") (pinfunction "1_1") (pintype "input"))
    )
    (net (code "45") (name "RIGHT") (class "Default")
      (node (ref "CN3") (pin "4") (pinfunction "4_4") (pintype "unspecified"))
      (node (ref "H1") (pin "18") (pinfunction "18_18") (pintype "unspecified"))
      (node (ref "U1") (pin "28") (pinfunction "GPIO17_28") (pintype "bidirectional"))
    )
    (net (code "46") (name "RST") (class "Default")
      (node (ref "H2") (pin "4") (pinfunction "4_4") (pintype "unspecified"))
      (node (ref "U1") (pin "5") (pinfunction "GPIO3_5") (pintype "bidirectional"))
    )
    (net (code "47") (name "S1") (class "Default")
      (node (ref "CN4") (pin "5") (pinfunction "5_5") (pintype "unspecified"))
      (node (ref "H1") (pin "16") (pinfunction "16_16") (pintype "unspecified"))
      (node (ref "U1") (pin "18") (pinfunction "GPIO15_18") (pintype "bidirectional"))
    )
    (net (code "48") (name "S2") (class "Default")
      (node (ref "CN4") (pin "4") (pinfunction "4_4") (pintype "unspecified"))
      (node (ref "H1") (pin "14") (pinfunction "14_14") (pintype "unspecified"))
      (node (ref "SW3") (pin "3") (pinfunction "3_3") (pintype "unspecified"))
      (node (ref "U1") (pin "16") (pinfunction "GPIO13_16") (pintype "bidirectional"))
    )
    (net (code "49") (name "SCL") (class "Default")
      (node (ref "CN14") (pin "4") (pinfunction "4_4") (pintype "unspecified"))
      (node (ref "R12") (pin "1") (pinfunction "1_1") (pintype "input"))
      (node (ref "U1") (pin "3") (pinfunction "GPIO1_3") (pintype "bidirectional"))
    )
    (net (code "50") (name "SDA") (class "Default")
      (node (ref "CN14") (pin "3") (pinfunction "3_3") (pintype "unspecified"))
      (node (ref "R11") (pin "1") (pinfunction "1_1") (pintype "input"))
      (node (ref "U1") (pin "2") (pinfunction "GPIO0_2") (pintype "bidirectional"))
    )
    (net (code "51") (name "SWCLK") (class "Default")
      (node (ref "H3") (pin "1") (pinfunction "1_1") (pintype "input"))
      (node (ref "U1") (pin "24") (pinfunction "SWCLK_24") (pintype "output"))
    )
    (net (code "52") (name "SWD") (class "Default")
      (node (ref "H3") (pin "3") (pinfunction "3_3") (pintype "input"))
      (node (ref "U1") (pin "25") (pinfunction "SWD_25") (pintype "bidirectional"))
    )
    (net (code "53") (name "UP") (class "Default")
      (node (ref "CN3") (pin "2") (pinfunction "2_2") (pintype "unspecified"))
      (node (ref "H1") (pin "20") (pinfunction "20_20") (pintype "unspecified"))
      (node (ref "U1") (pin "30") (pinfunction "GPIO19_30") (pintype "bidirectional"))
    )
    (net (code "54") (name "USB_DM") (class "Default")
      (node (ref "D1") (pin "5") (pinfunction "5_5") (pintype "input"))
      (node (ref "H4") (pin "4") (pinfunction "4_4") (pintype "unspecified"))
      (node (ref "R4") (pin "2") (pinfunction "2_2") (pintype "input"))
      (node (ref "USB1") (pin "5") (pinfunction "DN2_5") (pintype "unspecified"))
      (node (ref "USB1") (pin "7") (pinfunction "DN1_7") (pintype "unspecified"))
    )
    (net (code "55") (name "USB_DP") (class "Default")
      (node (ref "D1") (pin "6") (pinfunction "6_6") (pintype "input"))
      (node (ref "H4") (pin "3") (pinfunction "3_3") (pintype "unspecified"))
      (node (ref "R3") (pin "1") (pinfunction "1_1") (pintype "input"))
      (node (ref "USB1") (pin "6") (pinfunction "DP1_6") (pintype "unspecified"))
      (node (ref "USB1") (pin "8") (pinfunction "DP2_8") (pintype "unspecified"))
    )
    (net (code "56") (name "VCC") (class "Default")
      (node (ref "D1") (pin "4") (pinfunction "4_4") (pintype "input"))
      (node (ref "R7") (pin "2") (pinfunction "2_2") (pintype "input"))
      (node (ref "USB1") (pin "11") (pinfunction "VBUS_11") (pintype "unspecified"))
      (node (ref "USB1") (pin "2") (pinfunction "VBUS_2") (pintype "unspecified"))
    )
    (net (code "57") (name "XIN") (class "Default")
      (node (ref "C2") (pin "2") (pinfunction "2_2") (pintype "input"))
      (node (ref "U1") (pin "20") (pinfunction "XIN_20") (pintype "input"))
      (node (ref "X1") (pin "1") (pinfunction "OSC1_1") (pintype "unspecified"))
    )
    (net (code "58") (name "XOUT") (class "Default")
      (node (ref "R5") (pin "2") (pinfunction "2_2") (pintype "input"))
      (node (ref "U1") (pin "21") (pinfunction "XOUT_21") (pintype "unspecified"))
    )
    (net (code "59") (name "unconnected-(D1-Pad1)") (class "Default")
      (node (ref "D1") (pin "1") (pinfunction "1_1") (pintype "input+no_connect"))
    )
    (net (code "60") (name "unconnected-(SW1-Pad2)") (class "Default")
      (node (ref "SW1") (pin "2") (pinfunction "2_2") (pintype "unspecified+no_connect"))
    )
    (net (code "61") (name "unconnected-(SW1-Pad4)") (class "Default")
      (node (ref "SW1") (pin "4") (pinfunction "4_4") (pintype "unspecified+no_connect"))
    )
    (net (code "62") (name "unconnected-(SW2-Pad1)") (class "Default")
      (node (ref "SW2") (pin "1") (pinfunction "1_1") (pintype "unspecified+no_connect"))
    )
    (net (code "63") (name "unconnected-(SW2-Pad4)") (class "Default")
      (node (ref "SW2") (pin "4") (pinfunction "4_4") (pintype "unspecified+no_connect"))
    )
    (net (code "64") (name "unconnected-(SW3-Pad1)") (class "Default")
      (node (ref "SW3") (pin "1") (pinfunction "1_1") (pintype "unspecified+no_connect"))
    )
    (net (code "65") (name "unconnected-(SW3-Pad4)") (class "Default")
      (node (ref "SW3") (pin "4") (pinfunction "4_4") (pintype "unspecified+no_connect"))
    )
    (net (code "66") (name "unconnected-(U4-NC-Pad1)") (class "Default")
      (node (ref "U4") (pin "1") (pinfunction "NC_1") (pintype "unspecified+no_connect"))
    )
    (net (code "67") (name "unconnected-(USB1-SBU1-Pad9)") (class "Default")
      (node (ref "USB1") (pin "9") (pinfunction "SBU1_9") (pintype "unspecified+no_connect"))
    )
    (net (code "68") (name "unconnected-(USB1-SBU2-Pad3)") (class "Default")
      (node (ref "USB1") (pin "3") (pinfunction "SBU2_3") (pintype "unspecified+no_connect"))
    )
    (net (code "69") (name "unconnected-(X1-GND-Pad2)") (class "Default")
      (node (ref "X1") (pin "2") (pinfunction "GND_2") (pintype "unspecified+no_connect"))
    )
    (net (code "70") (name "unconnected-(X1-GND-Pad4)") (class "Default")
      (node (ref "X1") (pin "4") (pinfunction "GND_4") (pintype "unspecified+no_connect"))
    )
  )
)
